# Jacdac_Pressure_Sensor-RevC.net
KiCad netlist of a schematic drawn in EAGLE
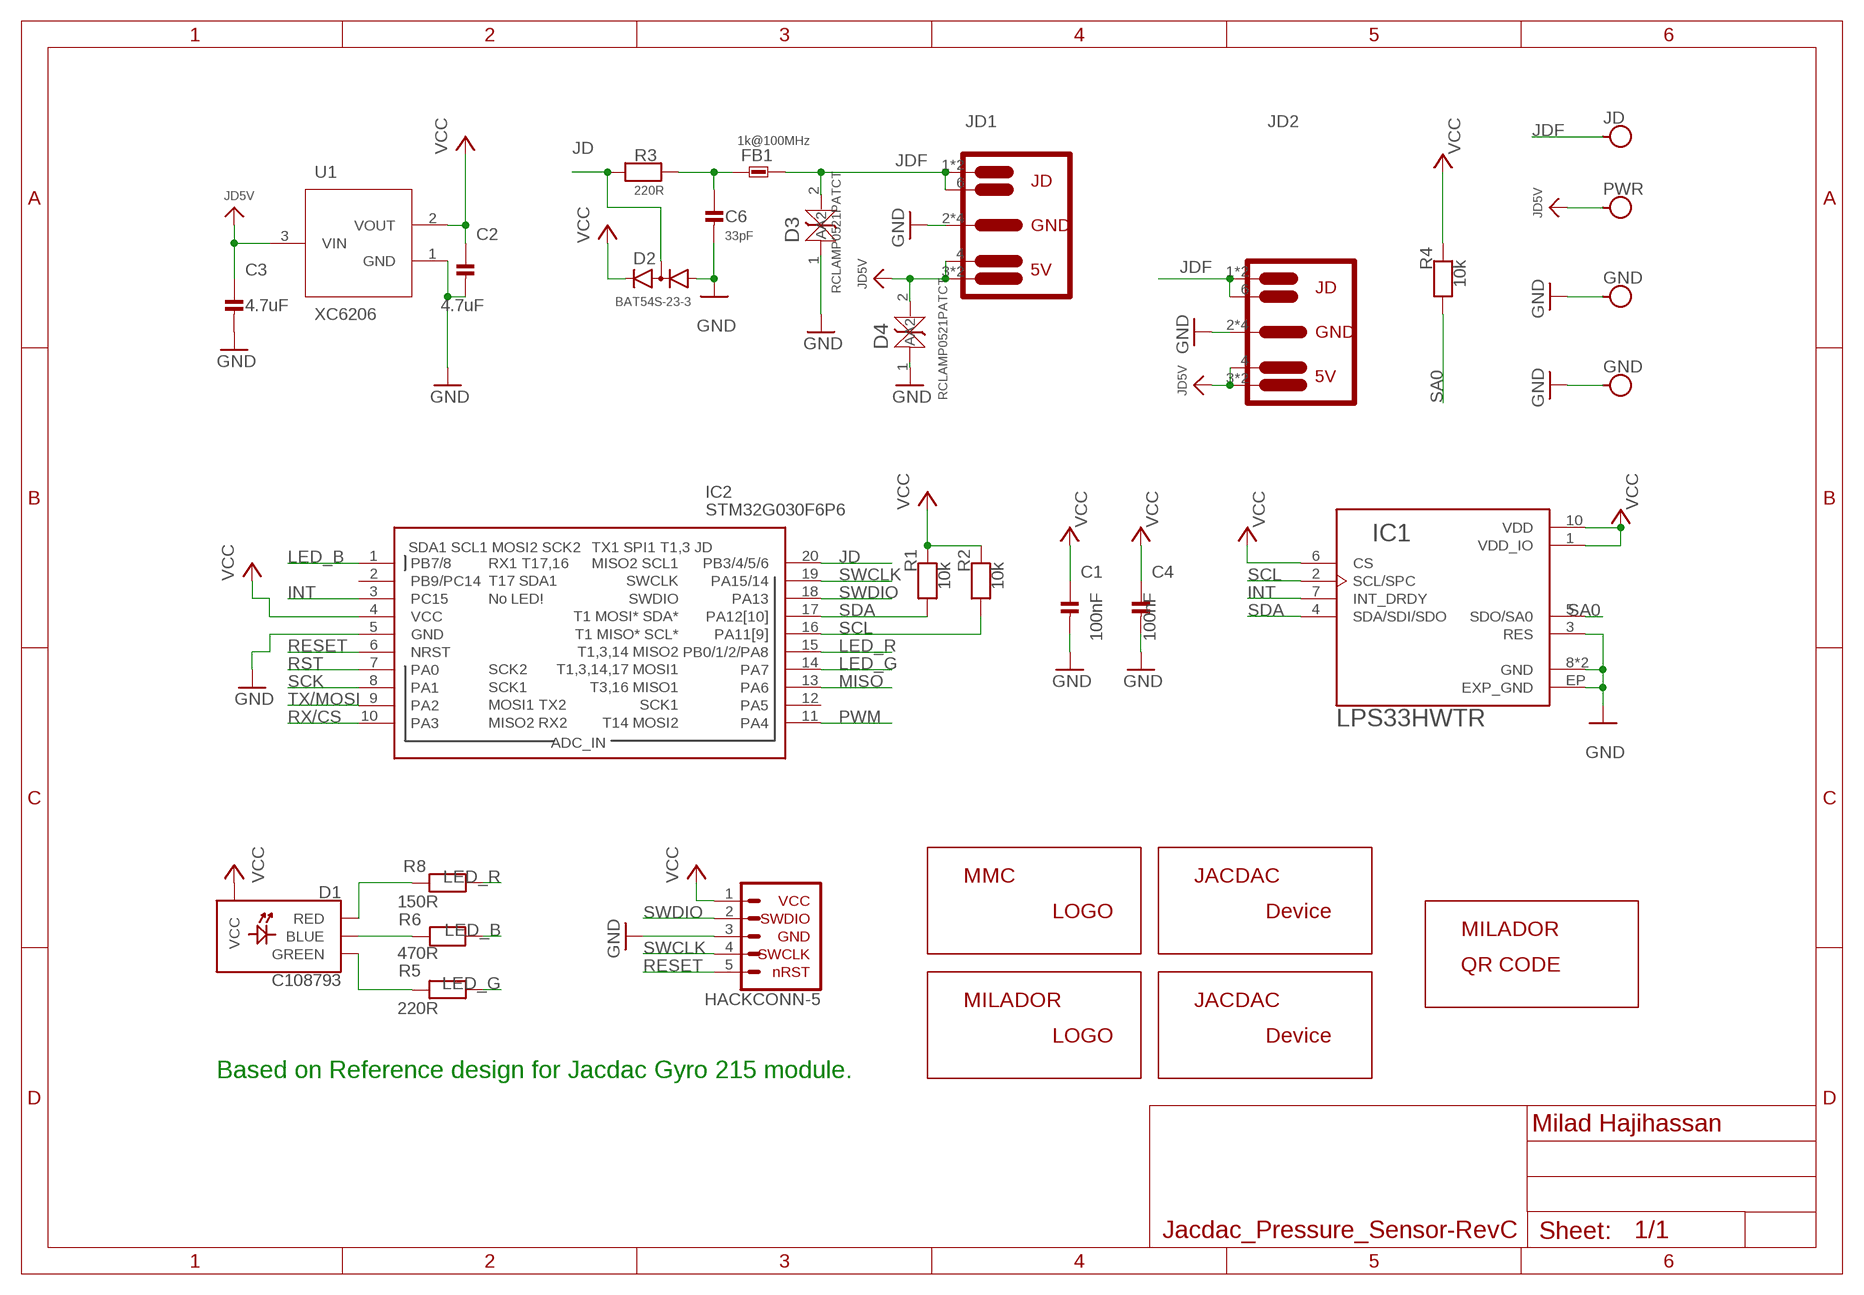
[diagram p0: schematic, sheet 1]

(export (version "E")
  (design (tool "Eeschema 10.0.6"))
  (components
    (comp (ref "C1")
      (value "100nF")
      (footprint "eagle-import:0402")
      (libsource (lib "eagle-import") (part "CAP_CERAMIC-0402"))
    )
    (comp (ref "C2")
      (value "4.7uF")
      (footprint "eagle-import:0402")
      (libsource (lib "eagle-import") (part "CAP_CERAMIC-0402"))
    )
    (comp (ref "C3")
      (value "4.7uF")
      (footprint "eagle-import:0402")
      (libsource (lib "eagle-import") (part "CAP_CERAMIC-0402"))
    )
    (comp (ref "C4")
      (value "100nF")
      (footprint "eagle-import:0402")
      (libsource (lib "eagle-import") (part "CAP_CERAMIC-0402"))
    )
    (comp (ref "C6")
      (value "33pF")
      (footprint "eagle-import:0402")
      (libsource (lib "eagle-import") (part "CAP_CERAMIC-0402"))
    )
    (comp (ref "D1")
      (value "C108793")
      (footprint "eagle-import:LED-RGB-2121")
      (libsource (lib "eagle-import") (part "LED-RGB-2121-CA"))
    )
    (comp (ref "D2")
      (value "BAT54S-23-3")
      (footprint "eagle-import:SOT23-3")
      (libsource (lib "eagle-import") (part "BAT54S-23-3"))
    )
    (comp (ref "D3")
      (value "RCLAMP0521PATCT")
      (footprint "eagle-import:DIODE-ZENER-0402")
      (fields (field (name "COPYRIGHT") "Copyright (C) 2021 Ultra Librarian. All rights reserved."))
      (libsource (lib "eagle-import") (part "DIODE-ZENER-AA-RCLAMP0521PATCT"))
    )
    (comp (ref "D4")
      (value "RCLAMP0521PATCT")
      (footprint "eagle-import:DIODE-ZENER-0402")
      (fields (field (name "COPYRIGHT") "Copyright (C) 2021 Ultra Librarian. All rights reserved."))
      (libsource (lib "eagle-import") (part "DIODE-ZENER-AA-RCLAMP0521PATCT"))
    )
    (comp (ref "FB1")
      (value "1k@100MHz")
      (footprint "eagle-import:0402")
      (libsource (lib "eagle-import") (part "FERRITE-BEAD-0402"))
    )
    (comp (ref "IC1")
      (value "LPS33HWTR")
      (footprint "eagle-import:PQFN60P330X330X290-11N")
      (fields (field (name "DIGI-KEY_PART_NUMBER") "497-17590-1-ND") (field (name "MF") "STMicroelectronics"))
      (libsource (lib "eagle-import") (part "LPS33HWTR"))
    )
    (comp (ref "IC2")
      (value "STM32G030F6P6")
      (footprint "eagle-import:SOP65P640X120-20N")
      (libsource (lib "eagle-import") (part "STM32G030F8P6"))
    )
    (comp (ref "J1")
      (value "JD")
      (footprint "eagle-import:M3-HOLE-DATA")
      (libsource (lib "eagle-import") (part "JACDAC-M3-DATA"))
    )
    (comp (ref "J2")
      (value "PWR")
      (footprint "eagle-import:M3-HOLE-PWR")
      (libsource (lib "eagle-import") (part "JACDAC-M3-PWR"))
    )
    (comp (ref "J3")
      (value "GND")
      (footprint "eagle-import:M3-HOLE-GND")
      (libsource (lib "eagle-import") (part "JACDAC-M3-GND"))
    )
    (comp (ref "J4")
      (value "GND")
      (footprint "eagle-import:M3-HOLE-GND")
      (libsource (lib "eagle-import") (part "JACDAC-M3-GND"))
    )
    (comp (ref "J5")
      (value "HACK-CONNECT-5")
      (footprint "eagle-import:HC5-22-62")
      (libsource (lib "eagle-import") (part "HACK-CONNECT-5"))
    )
    (comp (ref "JD1")
      (value "JACDAC-EDGE-OUTIE")
      (footprint "eagle-import:JD-EDGE-OUTIE")
      (libsource (lib "eagle-import") (part "JACDAC-EDGE-OUTIE"))
    )
    (comp (ref "JD2")
      (value "JACDAC-EDGE-OUTIE")
      (footprint "eagle-import:JD-EDGE-OUTIE")
      (libsource (lib "eagle-import") (part "JACDAC-EDGE-OUTIE"))
    )
    (comp (ref "LABEL_DEVICE")
      (value "MILADOR-JACDAC-DEVICE-PS")
      (footprint "eagle-import:JACDAC-PRESSURE-SENSOR")
      (libsource (lib "eagle-import") (part "MILADOR-JACDAC-DEVICE-PS"))
    )
    (comp (ref "LABEL_LOGO1")
      (value "MILADOR-LOGO-SM")
      (footprint "eagle-import:MILADOR_LOGO2")
      (libsource (lib "eagle-import") (part "MILADOR-LOGO-SM"))
    )
    (comp (ref "LABEL_LOGO2")
      (value "MMC_LOGO-XSM")
      (footprint "eagle-import:MMC_X-SMALL_LOGO")
      (libsource (lib "eagle-import") (part "MMC_LOGO-XSM"))
    )
    (comp (ref "LABEL_LPS33")
      (value "MILADOR-JACDAC-DEVICE-LPS33HW")
      (footprint "eagle-import:JACDAC-LPS33HW")
      (libsource (lib "eagle-import") (part "MILADOR-JACDAC-DEVICE-LPS33HW"))
    )
    (comp (ref "LABEL_QRCODE")
      (value "MILADOR-QR-CODE-JACDAC-GITHUB-PS")
      (footprint "eagle-import:MILADOR_QR_JACDAC_PS")
      (libsource (lib "eagle-import") (part "MILADOR-QR-CODE-JACDAC-GITHUB-PS"))
    )
    (comp (ref "R1")
      (value "10k")
      (footprint "eagle-import:0402")
      (libsource (lib "eagle-import") (part "RESISTOR-0402"))
    )
    (comp (ref "R2")
      (value "10k")
      (footprint "eagle-import:0402")
      (libsource (lib "eagle-import") (part "RESISTOR-0402"))
    )
    (comp (ref "R3")
      (value "220R")
      (footprint "eagle-import:0402")
      (libsource (lib "eagle-import") (part "RESISTOR-0402"))
    )
    (comp (ref "R4")
      (value "10k")
      (footprint "eagle-import:0402")
      (libsource (lib "eagle-import") (part "RESISTOR-0402"))
    )
    (comp (ref "R5")
      (value "220R")
      (footprint "eagle-import:0402")
      (libsource (lib "eagle-import") (part "RESISTOR-0402"))
    )
    (comp (ref "R6")
      (value "470R")
      (footprint "eagle-import:0402")
      (libsource (lib "eagle-import") (part "RESISTOR-0402"))
    )
    (comp (ref "R8")
      (value "150R")
      (footprint "eagle-import:0402")
      (libsource (lib "eagle-import") (part "RESISTOR-0402"))
    )
    (comp (ref "U1")
      (value "XC6206")
      (footprint "eagle-import:SOT23-3-W")
      (libsource (lib "eagle-import") (part "XC6206"))
    )
  )
  (nets
    (net (code "1") (name "/INT") (class "Default")
      (node (ref "IC1") (pin "7") (pinfunction "INT_DRDY_7") (pintype "bidirectional"))
      (node (ref "IC2") (pin "3") (pinfunction "PC15_3") (pintype "bidirectional"))
    )
    (net (code "2") (name "/JD") (class "Default")
      (node (ref "D2") (pin "3") (pinfunction "C1A2_3") (pintype "passive"))
      (node (ref "IC2") (pin "20") (pinfunction "PB3/4/5/6_20") (pintype "bidirectional"))
      (node (ref "R3") (pin "1") (pinfunction "1_1") (pintype "passive"))
    )
    (net (code "3") (name "/JDF") (class "Default")
      (node (ref "D3") (pin "2") (pinfunction "A2_2") (pintype "passive"))
      (node (ref "FB1") (pin "2") (pinfunction "2_2") (pintype "passive"))
      (node (ref "J1") (pin "H") (pinfunction "P$1_H") (pintype "bidirectional"))
      (node (ref "JD1") (pin "1") (pinfunction "2_1") (pintype "bidirectional"))
      (node (ref "JD1") (pin "6") (pinfunction "6_6") (pintype "bidirectional"))
      (node (ref "JD1") (pin "P$3") (pinfunction "2_P$3") (pintype "bidirectional"))
      (node (ref "JD2") (pin "1") (pinfunction "2_1") (pintype "bidirectional"))
      (node (ref "JD2") (pin "6") (pinfunction "6_6") (pintype "bidirectional"))
      (node (ref "JD2") (pin "P$3") (pinfunction "2_P$3") (pintype "bidirectional"))
    )
    (net (code "4") (name "/LED_B") (class "Default")
      (node (ref "IC2") (pin "1") (pinfunction "PB7/8_1") (pintype "input"))
      (node (ref "R6") (pin "1") (pinfunction "1_1") (pintype "passive"))
    )
    (net (code "5") (name "/LED_G") (class "Default")
      (node (ref "IC2") (pin "14") (pinfunction "PA7_14") (pintype "bidirectional"))
      (node (ref "R5") (pin "1") (pinfunction "1_1") (pintype "passive"))
    )
    (net (code "6") (name "/LED_R") (class "Default")
      (node (ref "IC2") (pin "15") (pinfunction "PB0/1/2/PA8_15") (pintype "input"))
      (node (ref "R8") (pin "1") (pinfunction "1_1") (pintype "passive"))
    )
    (net (code "7") (name "/MISO") (class "Default")
      (node (ref "IC2") (pin "13") (pinfunction "PA6_13") (pintype "bidirectional"))
    )
    (net (code "8") (name "/PWM") (class "Default")
      (node (ref "IC2") (pin "11") (pinfunction "PA4_11") (pintype "bidirectional"))
    )
    (net (code "9") (name "/RESET") (class "Default")
      (node (ref "IC2") (pin "6") (pinfunction "NRST_6") (pintype "bidirectional"))
      (node (ref "J5") (pin "5") (pinfunction "NRST_5") (pintype "bidirectional"))
    )
    (net (code "10") (name "/RST") (class "Default")
      (node (ref "IC2") (pin "7") (pinfunction "PA0_7") (pintype "bidirectional"))
    )
    (net (code "11") (name "/RX{slash}CS") (class "Default")
      (node (ref "IC2") (pin "10") (pinfunction "PA3_10") (pintype "bidirectional"))
    )
    (net (code "12") (name "/SA0") (class "Default")
      (node (ref "IC1") (pin "5") (pinfunction "SDO/SA0_5") (pintype "output"))
      (node (ref "R4") (pin "1") (pinfunction "1_1") (pintype "passive"))
    )
    (net (code "13") (name "/SCK") (class "Default")
      (node (ref "IC2") (pin "8") (pinfunction "PA1_8") (pintype "bidirectional"))
    )
    (net (code "14") (name "/SCL") (class "Default")
      (node (ref "IC1") (pin "2") (pinfunction "SCL/SPC_2") (pintype "input"))
      (node (ref "IC2") (pin "16") (pinfunction "PA11[9]_16") (pintype "input"))
      (node (ref "R2") (pin "1") (pinfunction "1_1") (pintype "passive"))
    )
    (net (code "15") (name "/SDA") (class "Default")
      (node (ref "IC1") (pin "4") (pinfunction "SDA/SDI/SDO_4") (pintype "bidirectional"))
      (node (ref "IC2") (pin "17") (pinfunction "PA12[10]_17") (pintype "bidirectional"))
      (node (ref "R1") (pin "1") (pinfunction "1_1") (pintype "passive"))
    )
    (net (code "16") (name "/SWCLK") (class "Default")
      (node (ref "IC2") (pin "19") (pinfunction "PA15/14_19") (pintype "bidirectional"))
      (node (ref "J5") (pin "4") (pinfunction "SWCLK_4") (pintype "input"))
    )
    (net (code "17") (name "/SWDIO") (class "Default")
      (node (ref "IC2") (pin "18") (pinfunction "PA13_18") (pintype "bidirectional"))
      (node (ref "J5") (pin "2") (pinfunction "SWDIO_2") (pintype "input"))
    )
    (net (code "18") (name "/TX{slash}MOSI") (class "Default")
      (node (ref "IC2") (pin "9") (pinfunction "PA2_9") (pintype "bidirectional"))
    )
    (net (code "19") (name "GND") (class "Default")
      (node (ref "C1") (pin "2") (pinfunction "2_2") (pintype "passive"))
      (node (ref "C2") (pin "2") (pinfunction "2_2") (pintype "passive"))
      (node (ref "C3") (pin "2") (pinfunction "2_2") (pintype "passive"))
      (node (ref "C4") (pin "2") (pinfunction "2_2") (pintype "passive"))
      (node (ref "C6") (pin "2") (pinfunction "2_2") (pintype "passive"))
      (node (ref "D2") (pin "1") (pinfunction "A1_1") (pintype "passive"))
      (node (ref "D3") (pin "1") (pinfunction "A_1") (pintype "passive"))
      (node (ref "D4") (pin "1") (pinfunction "A_1") (pintype "passive"))
      (node (ref "IC1") (pin "3") (pinfunction "RES_3") (pintype "passive"))
      (node (ref "IC1") (pin "8") (pinfunction "GND_8") (pintype "power_in"))
      (node (ref "IC1") (pin "9") (pinfunction "GND_9") (pintype "power_in"))
      (node (ref "IC1") (pin "EP") (pinfunction "EXP_GND_EP") (pintype "power_in"))
      (node (ref "IC2") (pin "5") (pinfunction "GND_5") (pintype "power_in"))
      (node (ref "J3") (pin "H") (pinfunction "P$1_H") (pintype "bidirectional"))
      (node (ref "J4") (pin "H") (pinfunction "P$1_H") (pintype "bidirectional"))
      (node (ref "J5") (pin "3") (pinfunction "GND_3") (pintype "power_in"))
      (node (ref "JD1") (pin "2") (pinfunction "1_2") (pintype "power_in"))
      (node (ref "JD1") (pin "5") (pinfunction "1_5") (pintype "power_in"))
      (node (ref "JD1") (pin "P$2") (pinfunction "1_P$2") (pintype "power_in"))
      (node (ref "JD1") (pin "P$4") (pinfunction "1_P$4") (pintype "power_in"))
      (node (ref "JD2") (pin "2") (pinfunction "1_2") (pintype "power_in"))
      (node (ref "JD2") (pin "5") (pinfunction "1_5") (pintype "power_in"))
      (node (ref "JD2") (pin "P$2") (pinfunction "1_P$2") (pintype "power_in"))
      (node (ref "JD2") (pin "P$4") (pinfunction "1_P$4") (pintype "power_in"))
      (node (ref "U1") (pin "1") (pinfunction "GND_1") (pintype "passive"))
    )
    (net (code "20") (name "JD5V") (class "Default")
      (node (ref "C3") (pin "1") (pinfunction "1_1") (pintype "passive"))
      (node (ref "D4") (pin "2") (pinfunction "A2_2") (pintype "passive"))
      (node (ref "J2") (pin "H") (pinfunction "P$1_H") (pintype "bidirectional"))
      (node (ref "JD1") (pin "3") (pinfunction "3_3") (pintype "power_in"))
      (node (ref "JD1") (pin "4") (pinfunction "4_4") (pintype "power_in"))
      (node (ref "JD1") (pin "P$1") (pinfunction "3_P$1") (pintype "power_in"))
      (node (ref "JD2") (pin "3") (pinfunction "3_3") (pintype "power_in"))
      (node (ref "JD2") (pin "4") (pinfunction "4_4") (pintype "power_in"))
      (node (ref "JD2") (pin "P$1") (pinfunction "3_P$1") (pintype "power_in"))
      (node (ref "U1") (pin "3") (pinfunction "VIN_3") (pintype "input"))
    )
    (net (code "21") (name "Net-(C6-Pad1)") (class "Default")
      (node (ref "C6") (pin "1") (pinfunction "1_1") (pintype "passive"))
      (node (ref "FB1") (pin "1") (pinfunction "1_1") (pintype "passive"))
      (node (ref "R3") (pin "2") (pinfunction "2_2") (pintype "passive"))
    )
    (net (code "22") (name "Net-(D1-BLUE)") (class "Default")
      (node (ref "D1") (pin "B-") (pinfunction "BLUE_B-") (pintype "bidirectional"))
      (node (ref "R6") (pin "2") (pinfunction "2_2") (pintype "passive"))
    )
    (net (code "23") (name "Net-(D1-GREEN)") (class "Default")
      (node (ref "D1") (pin "G-") (pinfunction "GREEN_G-") (pintype "bidirectional"))
      (node (ref "R5") (pin "2") (pinfunction "2_2") (pintype "passive"))
    )
    (net (code "24") (name "Net-(D1-RED)") (class "Default")
      (node (ref "D1") (pin "R-") (pinfunction "RED_R-") (pintype "bidirectional"))
      (node (ref "R8") (pin "2") (pinfunction "2_2") (pintype "passive"))
    )
    (net (code "25") (name "VCC") (class "Default")
      (node (ref "C1") (pin "1") (pinfunction "1_1") (pintype "passive"))
      (node (ref "C2") (pin "1") (pinfunction "1_1") (pintype "passive"))
      (node (ref "C4") (pin "1") (pinfunction "1_1") (pintype "passive"))
      (node (ref "D1") (pin "PLUS") (pinfunction "VCC_PLUS") (pintype "bidirectional"))
      (node (ref "D2") (pin "2") (pinfunction "C2_2") (pintype "passive"))
      (node (ref "IC1") (pin "1") (pinfunction "VDD_IO_1") (pintype "power_in"))
      (node (ref "IC1") (pin "10") (pinfunction "VDD_10") (pintype "power_in"))
      (node (ref "IC1") (pin "6") (pinfunction "CS_6") (pintype "bidirectional"))
      (node (ref "IC2") (pin "4") (pinfunction "VCC_4") (pintype "power_in"))
      (node (ref "J5") (pin "1") (pinfunction "VCC_1") (pintype "passive"))
      (node (ref "R1") (pin "2") (pinfunction "2_2") (pintype "passive"))
      (node (ref "R2") (pin "2") (pinfunction "2_2") (pintype "passive"))
      (node (ref "R4") (pin "2") (pinfunction "2_2") (pintype "passive"))
      (node (ref "U1") (pin "2") (pinfunction "VOUT_2") (pintype "power_in"))
    )
    (net (code "26") (name "unconnected-(IC2-PA5-Pad12)") (class "Default")
      (node (ref "IC2") (pin "12") (pinfunction "PA5_12") (pintype "bidirectional"))
    )
    (net (code "27") (name "unconnected-(IC2-PB9{slash}PC14-Pad2)") (class "Default")
      (node (ref "IC2") (pin "2") (pinfunction "PB9/PC14_2") (pintype "bidirectional"))
    )
  )
)
